# S02-DRIVER.net
KiCad netlist of a schematic drawn in Altium Designer
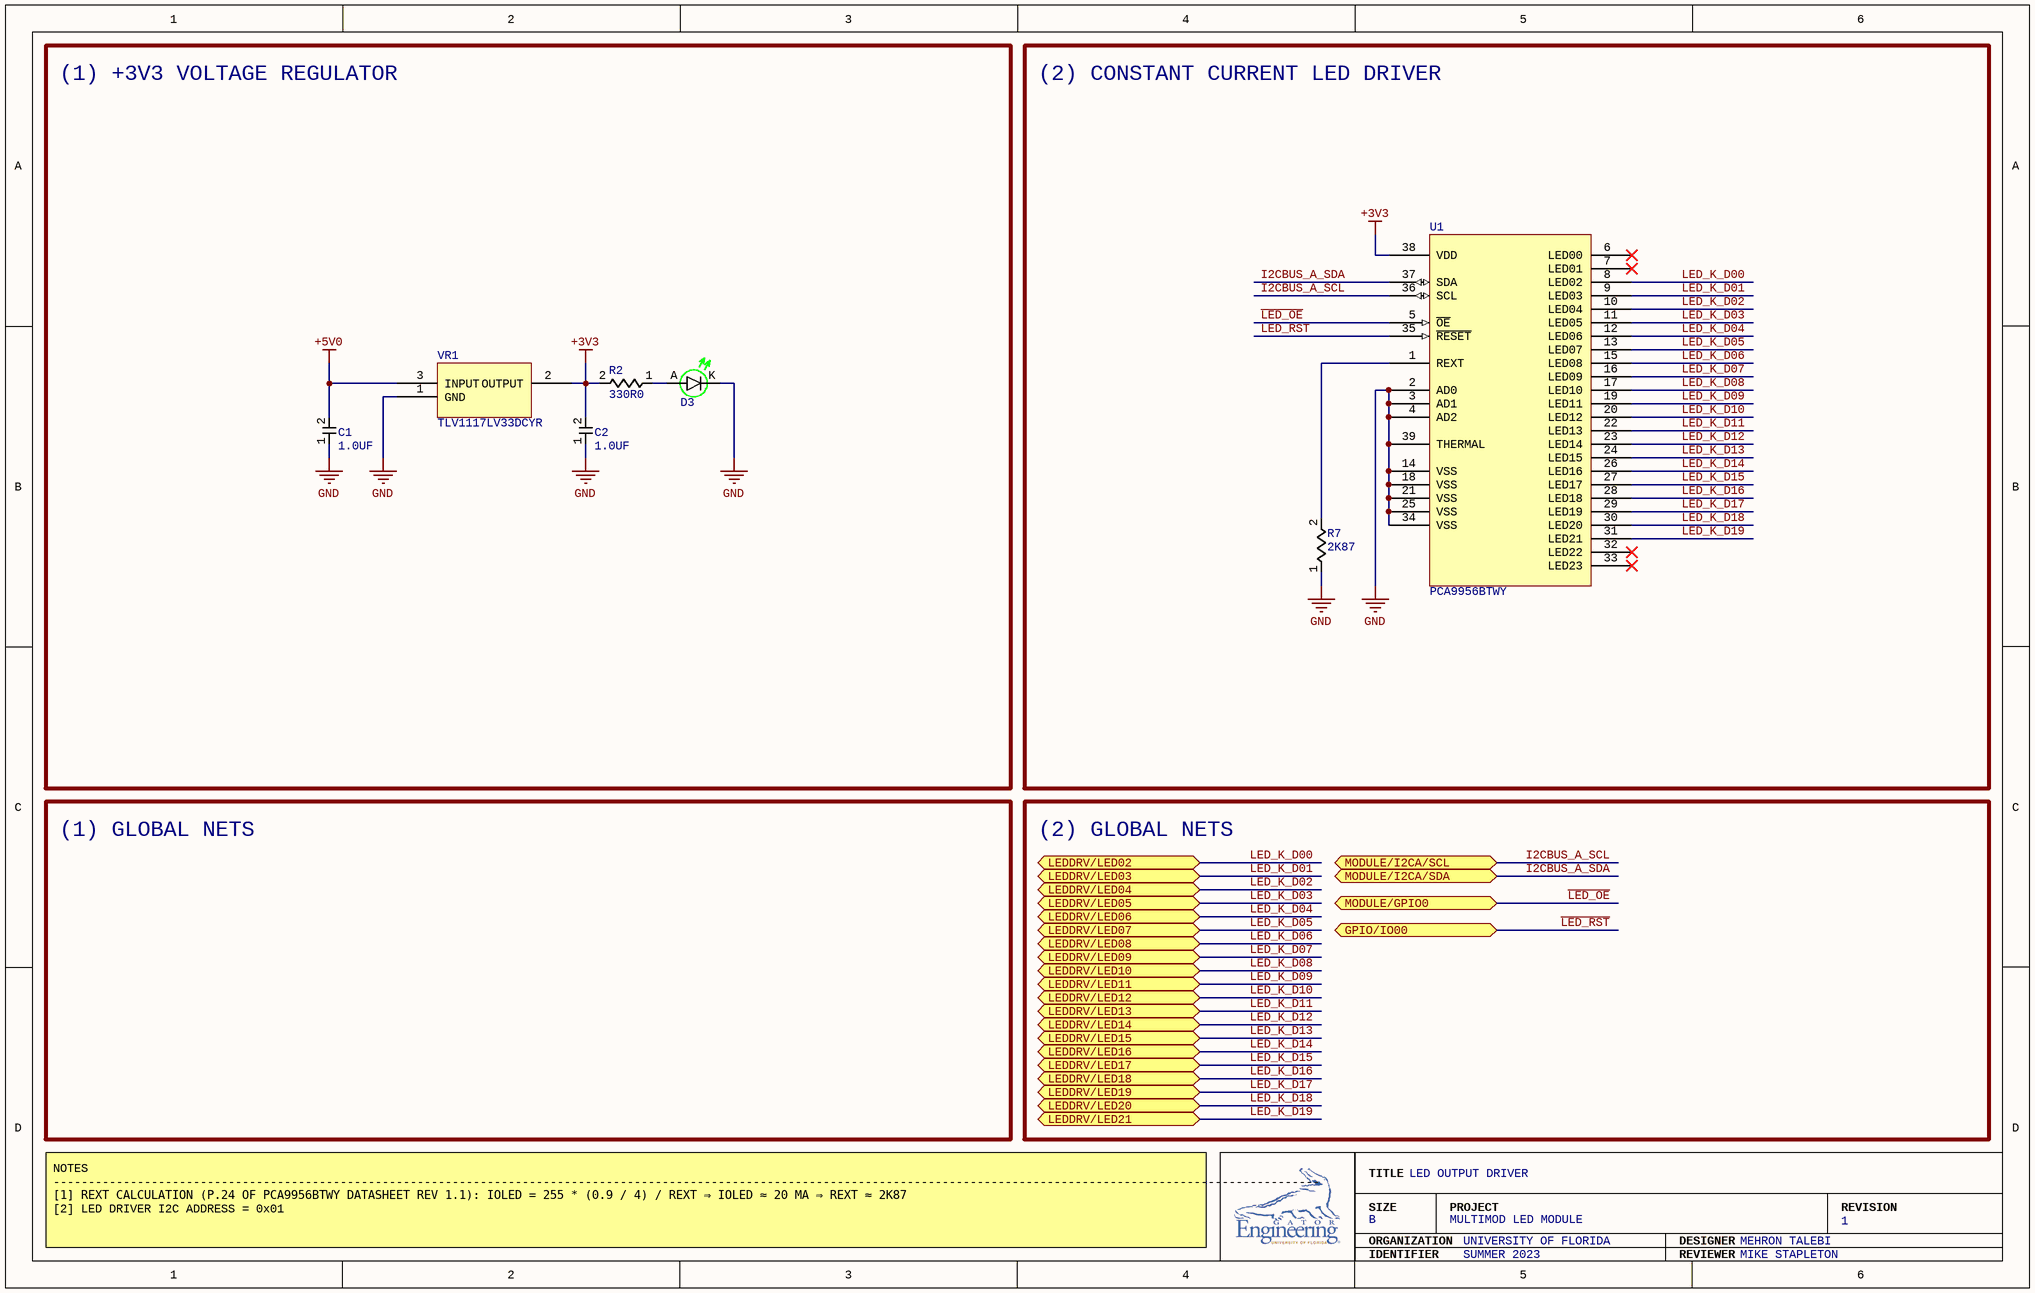
[diagram p0: S02-DRIVER.SchDoc]

(export (version "E")
  (design (tool "Eeschema 10.0.6"))
  (components
    (comp (ref "C1")
      (value "1.0UF")
      (footprint "CL21B105KAFNFNE")
      (description "CAP CER 1UF 25V X7R 0805")
      (fields (field (name "TOLERANCE") "±10%"))
      (libsource (lib "Master") (part "CL21B105KAFNFNE"))
    )
    (comp (ref "C2")
      (value "1.0UF")
      (footprint "CL21B105KAFNFNE")
      (description "CAP CER 1UF 25V X7R 0805")
      (fields (field (name "TOLERANCE") "±10%"))
      (libsource (lib "Master") (part "CL21B105KAFNFNE"))
    )
    (comp (ref "D3")
      (value "LTST-C171GKT")
      (footprint "LTST-C171GKT")
      (description "LED GREEN CLEAR CHIP SMD")
      (libsource (lib "Master") (part "LTST-C171GKT"))
    )
    (comp (ref "R2")
      (value "330R0")
      (footprint "RC0805FR-7W330RL")
      (description "RES 330 OHM 1% 1/4W 0805")
      (fields (field (name "TOLERANCE") "±1%"))
      (libsource (lib "Master") (part "RC0805FR-7W330RL"))
    )
    (comp (ref "R7")
      (value "2K87")
      (footprint "RC0805FR-0710KL")
      (description "RES 2.87K OHM 1% 1/8W 0805")
      (fields (field (name "TOLERANCE") "±1%"))
      (libsource (lib "Master") (part "RC0805FR-072K87L"))
    )
    (comp (ref "U1")
      (value "PCA9956BTWY")
      (footprint "PCA9956BTWY")
      (description "IC LED DRV LIN PWM 65MA 38HTSSOP")
      (libsource (lib "Master") (part "PCA9956BTWY"))
    )
    (comp (ref "VR1")
      (value "TLV1117LV33DCYR")
      (footprint "TLV1117LV33DCYR")
      (description "IC REG LINEAR 3.3V 1A SOT223-4")
      (libsource (lib "Master") (part "TLV1117LV33DCYR"))
    )
  )
  (nets
    (net (code "1") (name "+3V3") (class "Default")
      (node (ref "C2") (pin "2") (pinfunction "2_2") (pintype "passive"))
      (node (ref "R2") (pin "2") (pinfunction "2_2") (pintype "passive"))
      (node (ref "U1") (pin "38") (pinfunction "VDD_38") (pintype "power_in"))
      (node (ref "VR1") (pin "2") (pinfunction "OUTPUT_2") (pintype "passive"))
    )
    (net (code "2") (name "+5V0") (class "Default")
      (node (ref "C1") (pin "2") (pinfunction "2_2") (pintype "passive"))
      (node (ref "VR1") (pin "3") (pinfunction "INPUT_3") (pintype "passive"))
    )
    (net (code "3") (name "/I2CBUS_A_SCL") (class "Default")
      (node (ref "U1") (pin "36") (pinfunction "SCL_36") (pintype "bidirectional"))
    )
    (net (code "4") (name "/I2CBUS_A_SDA") (class "Default")
      (node (ref "U1") (pin "37") (pinfunction "SDA_37") (pintype "bidirectional"))
    )
    (net (code "5") (name "/LED_K_D00") (class "Default")
      (node (ref "U1") (pin "8") (pinfunction "LED02_8") (pintype "passive"))
    )
    (net (code "6") (name "/LED_K_D01") (class "Default")
      (node (ref "U1") (pin "9") (pinfunction "LED03_9") (pintype "passive"))
    )
    (net (code "7") (name "/LED_K_D02") (class "Default")
      (node (ref "U1") (pin "10") (pinfunction "LED04_10") (pintype "passive"))
    )
    (net (code "8") (name "/LED_K_D03") (class "Default")
      (node (ref "U1") (pin "11") (pinfunction "LED05_11") (pintype "passive"))
    )
    (net (code "9") (name "/LED_K_D04") (class "Default")
      (node (ref "U1") (pin "12") (pinfunction "LED06_12") (pintype "passive"))
    )
    (net (code "10") (name "/LED_K_D05") (class "Default")
      (node (ref "U1") (pin "13") (pinfunction "LED07_13") (pintype "passive"))
    )
    (net (code "11") (name "/LED_K_D06") (class "Default")
      (node (ref "U1") (pin "15") (pinfunction "LED08_15") (pintype "passive"))
    )
    (net (code "12") (name "/LED_K_D07") (class "Default")
      (node (ref "U1") (pin "16") (pinfunction "LED09_16") (pintype "passive"))
    )
    (net (code "13") (name "/LED_K_D08") (class "Default")
      (node (ref "U1") (pin "17") (pinfunction "LED10_17") (pintype "passive"))
    )
    (net (code "14") (name "/LED_K_D09") (class "Default")
      (node (ref "U1") (pin "19") (pinfunction "LED11_19") (pintype "passive"))
    )
    (net (code "15") (name "/LED_K_D10") (class "Default")
      (node (ref "U1") (pin "20") (pinfunction "LED12_20") (pintype "passive"))
    )
    (net (code "16") (name "/LED_K_D11") (class "Default")
      (node (ref "U1") (pin "22") (pinfunction "LED13_22") (pintype "passive"))
    )
    (net (code "17") (name "/LED_K_D12") (class "Default")
      (node (ref "U1") (pin "23") (pinfunction "LED14_23") (pintype "passive"))
    )
    (net (code "18") (name "/LED_K_D13") (class "Default")
      (node (ref "U1") (pin "24") (pinfunction "LED15_24") (pintype "passive"))
    )
    (net (code "19") (name "/LED_K_D14") (class "Default")
      (node (ref "U1") (pin "26") (pinfunction "LED16_26") (pintype "passive"))
    )
    (net (code "20") (name "/LED_K_D15") (class "Default")
      (node (ref "U1") (pin "27") (pinfunction "LED17_27") (pintype "passive"))
    )
    (net (code "21") (name "/LED_K_D16") (class "Default")
      (node (ref "U1") (pin "28") (pinfunction "LED18_28") (pintype "passive"))
    )
    (net (code "22") (name "/LED_K_D17") (class "Default")
      (node (ref "U1") (pin "29") (pinfunction "LED19_29") (pintype "passive"))
    )
    (net (code "23") (name "/LED_K_D18") (class "Default")
      (node (ref "U1") (pin "30") (pinfunction "LED20_30") (pintype "passive"))
    )
    (net (code "24") (name "/LED_K_D19") (class "Default")
      (node (ref "U1") (pin "31") (pinfunction "LED21_31") (pintype "passive"))
    )
    (net (code "25") (name "/LED_OE") (class "Default")
      (node (ref "U1") (pin "5") (pinfunction "OE_5") (pintype "input"))
    )
    (net (code "26") (name "/LED_RST") (class "Default")
      (node (ref "U1") (pin "35") (pinfunction "RESET_35") (pintype "input"))
    )
    (net (code "27") (name "GND") (class "Default")
      (node (ref "C1") (pin "1") (pinfunction "1_1") (pintype "passive"))
      (node (ref "C2") (pin "1") (pinfunction "1_1") (pintype "passive"))
      (node (ref "D3") (pin "K") (pinfunction "K_K") (pintype "passive"))
      (node (ref "R7") (pin "1") (pinfunction "1_1") (pintype "passive"))
      (node (ref "U1") (pin "14") (pinfunction "VSS_14") (pintype "power_in"))
      (node (ref "U1") (pin "18") (pinfunction "VSS_18") (pintype "power_in"))
      (node (ref "U1") (pin "2") (pinfunction "AD0_2") (pintype "passive"))
      (node (ref "U1") (pin "21") (pinfunction "VSS_21") (pintype "power_in"))
      (node (ref "U1") (pin "25") (pinfunction "VSS_25") (pintype "power_in"))
      (node (ref "U1") (pin "3") (pinfunction "AD1_3") (pintype "passive"))
      (node (ref "U1") (pin "34") (pinfunction "VSS_34") (pintype "power_in"))
      (node (ref "U1") (pin "39") (pinfunction "THERMAL_39") (pintype "passive"))
      (node (ref "U1") (pin "4") (pinfunction "AD2_4") (pintype "passive"))
      (node (ref "VR1") (pin "1") (pinfunction "GND_1") (pintype "passive"))
    )
    (net (code "28") (name "Net-(D3-PadA)") (class "Default")
      (node (ref "D3") (pin "A") (pinfunction "A_A") (pintype "passive"))
      (node (ref "R2") (pin "1") (pinfunction "1_1") (pintype "passive"))
    )
    (net (code "29") (name "Net-(U1-REXT)") (class "Default")
      (node (ref "R7") (pin "2") (pinfunction "2_2") (pintype "passive"))
      (node (ref "U1") (pin "1") (pinfunction "REXT_1") (pintype "passive"))
    )
    (net (code "30") (name "unconnected-(U1-LED00-Pad6)") (class "Default")
      (node (ref "U1") (pin "6") (pinfunction "LED00_6") (pintype "passive+no_connect"))
    )
    (net (code "31") (name "unconnected-(U1-LED01-Pad7)") (class "Default")
      (node (ref "U1") (pin "7") (pinfunction "LED01_7") (pintype "passive+no_connect"))
    )
    (net (code "32") (name "unconnected-(U1-LED22-Pad32)") (class "Default")
      (node (ref "U1") (pin "32") (pinfunction "LED22_32") (pintype "passive+no_connect"))
    )
    (net (code "33") (name "unconnected-(U1-LED23-Pad33)") (class "Default")
      (node (ref "U1") (pin "33") (pinfunction "LED23_33") (pintype "passive+no_connect"))
    )
  )
)
